# CAN.net
KiCad netlist of a schematic drawn in Altium Designer
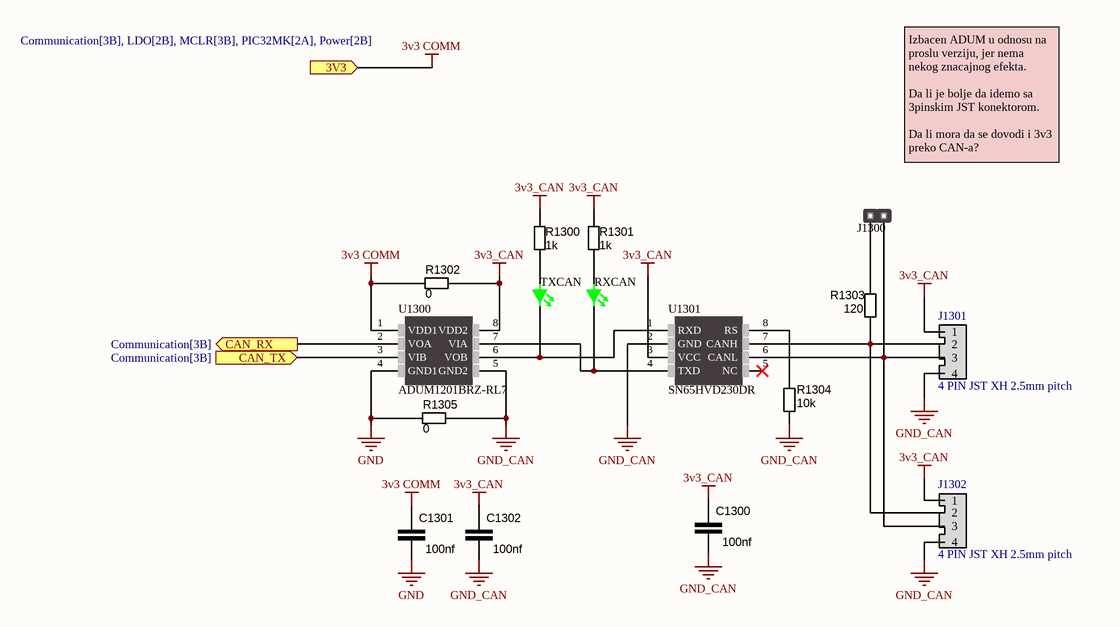
[diagram p0: CAN.SchDoc]

(export (version "E")
  (design (tool "Eeschema 10.0.6"))
  (components
    (comp (ref "C1300")
      (value "100nf")
      (footprint "CAP_0603")
      (description "CAP CER 100nF 0603 25V X7R")
      (libsource (lib "CapacitorsIntegrated") (part "C000007"))
    )
    (comp (ref "C1301")
      (value "100nf")
      (footprint "CAP_0603")
      (description "CAP CER 100nF 0603 25V X7R")
      (libsource (lib "CapacitorsIntegrated") (part "C000007"))
    )
    (comp (ref "C1302")
      (value "100nf")
      (footprint "CAP_0603")
      (description "CAP CER 100nF 0603 25V X7R")
      (libsource (lib "CapacitorsIntegrated") (part "C000007"))
    )
    (comp (ref "J1300") (value "*") (footprint "HM1x2") (libsource (lib "motion_board") (part "HEADER_1x2")))
    (comp (ref "J1301")
      (value "4 PIN JST XH 2.5mm pitch")
      (footprint "Connectors:JST4PIN")
      (libsource (lib "Connectors") (part "JST4PIN"))
    )
    (comp (ref "J1302")
      (value "4 PIN JST XH 2.5mm pitch")
      (footprint "Connectors:JST4PIN")
      (libsource (lib "Connectors") (part "JST4PIN"))
    )
    (comp (ref "R1300")
      (value "1k")
      (footprint "RES_0603")
      (description "RES 1k OHM 1% 1/10W 0603")
      (libsource (lib "") (part "R000004_1"))
    )
    (comp (ref "R1301")
      (value "1k")
      (footprint "RES_0603")
      (description "RES 1k OHM 1% 1/10W 0603")
      (libsource (lib "") (part "R000004_1"))
    )
    (comp (ref "R1302")
      (value "0")
      (footprint "RES_0603")
      (description "RES 0 OHM 1% 1/10W 0603")
      (libsource (lib "") (part "R000004_2"))
    )
    (comp (ref "R1303")
      (value "120")
      (footprint "RES_0603")
      (description "RES 120 OHM 1% 1/10W 0603")
      (libsource (lib "") (part "R000004_1"))
    )
    (comp (ref "R1304")
      (value "10k")
      (footprint "RES_0603")
      (description "RES 10k OHM 1% 1/10W 0603")
      (libsource (lib "") (part "R000004_1"))
    )
    (comp (ref "R1305")
      (value "0")
      (footprint "RES_0603")
      (description "RES 10k OHM 1% 1/10W 0603")
      (libsource (lib "ResistorsIntegrated") (part "R000004"))
    )
    (comp (ref "RXCAN")
      (value "GREEN LED")
      (footprint "DIOC1608X04N")
      (description "LED GREEN DIFFUSED 0603 SMD")
      (libsource (lib "Miscellaneous_Lib1") (part "00000001"))
    )
    (comp (ref "TXCAN")
      (value "GREEN LED")
      (footprint "DIOC1608X04N")
      (description "LED GREEN DIFFUSED 0603 SMD")
      (libsource (lib "Miscellaneous_Lib1") (part "00000001"))
    )
    (comp (ref "U1300")
      (value "ADUM1201BRZ-RL7")
      (footprint "SOIC-8")
      (description "DGTL ISO 2.5KV GEN PURP 8SOIC")
      (libsource (lib "motion_board") (part "ADUM1201BRZ"))
    )
    (comp (ref "U1301")
      (value "SN65HVD230DR")
      (footprint "SOIC-8")
      (description "IC EMC CAN TRANSCEIVER 8-SOIC")
      (libsource (lib "motion_board") (part "SN65HVD230"))
    )
  )
  (nets
    (net (code "1") (name "/CAN_RX") (class "Default")
      (node (ref "U1300") (pin "2") (pinfunction "VOA_2") (pintype "passive"))
    )
    (net (code "2") (name "/CAN_TX") (class "Default")
      (node (ref "U1300") (pin "3") (pinfunction "VIB_3") (pintype "passive"))
    )
    (net (code "3") (name "3v3 COMM") (class "Default")
      (node (ref "C1301") (pin "2") (pinfunction "2_2") (pintype "passive"))
      (node (ref "R1302") (pin "1") (pinfunction "1_1") (pintype "passive"))
      (node (ref "U1300") (pin "1") (pinfunction "VDD1_1") (pintype "passive"))
    )
    (net (code "4") (name "3v3_CAN") (class "Default")
      (node (ref "C1300") (pin "2") (pinfunction "2_2") (pintype "passive"))
      (node (ref "C1302") (pin "2") (pinfunction "2_2") (pintype "passive"))
      (node (ref "J1301") (pin "1") (pinfunction "1_1") (pintype "passive"))
      (node (ref "J1302") (pin "1") (pinfunction "1_1") (pintype "passive"))
      (node (ref "R1300") (pin "2") (pinfunction "2_2") (pintype "passive"))
      (node (ref "R1301") (pin "2") (pinfunction "2_2") (pintype "passive"))
      (node (ref "R1302") (pin "2") (pinfunction "2_2") (pintype "passive"))
      (node (ref "U1300") (pin "8") (pinfunction "VDD2_8") (pintype "passive"))
      (node (ref "U1301") (pin "3") (pinfunction "VCC_3") (pintype "passive"))
    )
    (net (code "5") (name "GND") (class "Default")
      (node (ref "C1301") (pin "1") (pinfunction "1_1") (pintype "passive"))
      (node (ref "R1305") (pin "2") (pinfunction "2_2") (pintype "passive"))
      (node (ref "U1300") (pin "4") (pinfunction "GND1_4") (pintype "passive"))
    )
    (net (code "6") (name "GND_CAN") (class "Default")
      (node (ref "C1300") (pin "1") (pinfunction "1_1") (pintype "passive"))
      (node (ref "C1302") (pin "1") (pinfunction "1_1") (pintype "passive"))
      (node (ref "J1301") (pin "4") (pinfunction "4_4") (pintype "passive"))
      (node (ref "J1302") (pin "4") (pinfunction "4_4") (pintype "passive"))
      (node (ref "R1304") (pin "1") (pinfunction "1_1") (pintype "passive"))
      (node (ref "R1305") (pin "1") (pinfunction "1_1") (pintype "passive"))
      (node (ref "U1300") (pin "5") (pinfunction "GND2_5") (pintype "passive"))
      (node (ref "U1301") (pin "2") (pinfunction "GND_2") (pintype "passive"))
    )
    (net (code "7") (name "Net-(J1300-Pad1)") (class "Default")
      (node (ref "J1300") (pin "1") (pinfunction "1_1") (pintype "passive"))
      (node (ref "R1303") (pin "2") (pinfunction "2_2") (pintype "passive"))
    )
    (net (code "8") (name "Net-(R1300-Pad1)") (class "Default")
      (node (ref "R1300") (pin "1") (pinfunction "1_1") (pintype "passive"))
      (node (ref "TXCAN") (pin "1") (pinfunction "1_1") (pintype "passive"))
    )
    (net (code "9") (name "Net-(R1301-Pad1)") (class "Default")
      (node (ref "R1301") (pin "1") (pinfunction "1_1") (pintype "passive"))
      (node (ref "RXCAN") (pin "1") (pinfunction "1_1") (pintype "passive"))
    )
    (net (code "10") (name "Net-(U1300-VIA)") (class "Default")
      (node (ref "RXCAN") (pin "2") (pinfunction "2_2") (pintype "passive"))
      (node (ref "U1300") (pin "7") (pinfunction "VIA_7") (pintype "passive"))
      (node (ref "U1301") (pin "4") (pinfunction "TXD_4") (pintype "passive"))
    )
    (net (code "11") (name "Net-(U1300-VOB)") (class "Default")
      (node (ref "TXCAN") (pin "2") (pinfunction "2_2") (pintype "passive"))
      (node (ref "U1300") (pin "6") (pinfunction "VOB_6") (pintype "passive"))
      (node (ref "U1301") (pin "1") (pinfunction "RXD_1") (pintype "passive"))
    )
    (net (code "12") (name "Net-(U1301-CANH)") (class "Default")
      (node (ref "J1301") (pin "2") (pinfunction "2_2") (pintype "passive"))
      (node (ref "J1302") (pin "2") (pinfunction "2_2") (pintype "passive"))
      (node (ref "R1303") (pin "1") (pinfunction "1_1") (pintype "passive"))
      (node (ref "U1301") (pin "7") (pinfunction "CANH_7") (pintype "passive"))
    )
    (net (code "13") (name "Net-(U1301-CANL)") (class "Default")
      (node (ref "J1300") (pin "2") (pinfunction "1_2") (pintype "passive"))
      (node (ref "J1301") (pin "3") (pinfunction "3_3") (pintype "passive"))
      (node (ref "J1302") (pin "3") (pinfunction "3_3") (pintype "passive"))
      (node (ref "U1301") (pin "6") (pinfunction "CANL_6") (pintype "passive"))
    )
    (net (code "14") (name "Net-(U1301-RS)") (class "Default")
      (node (ref "R1304") (pin "2") (pinfunction "2_2") (pintype "passive"))
      (node (ref "U1301") (pin "8") (pinfunction "RS_8") (pintype "passive"))
    )
    (net (code "15") (name "unconnected-(U1301-NC-Pad5)") (class "Default")
      (node (ref "U1301") (pin "5") (pinfunction "NC_5") (pintype "passive+no_connect"))
    )
  )
)
